# J6_output.net
KiCad netlist of a schematic drawn in EAGLE
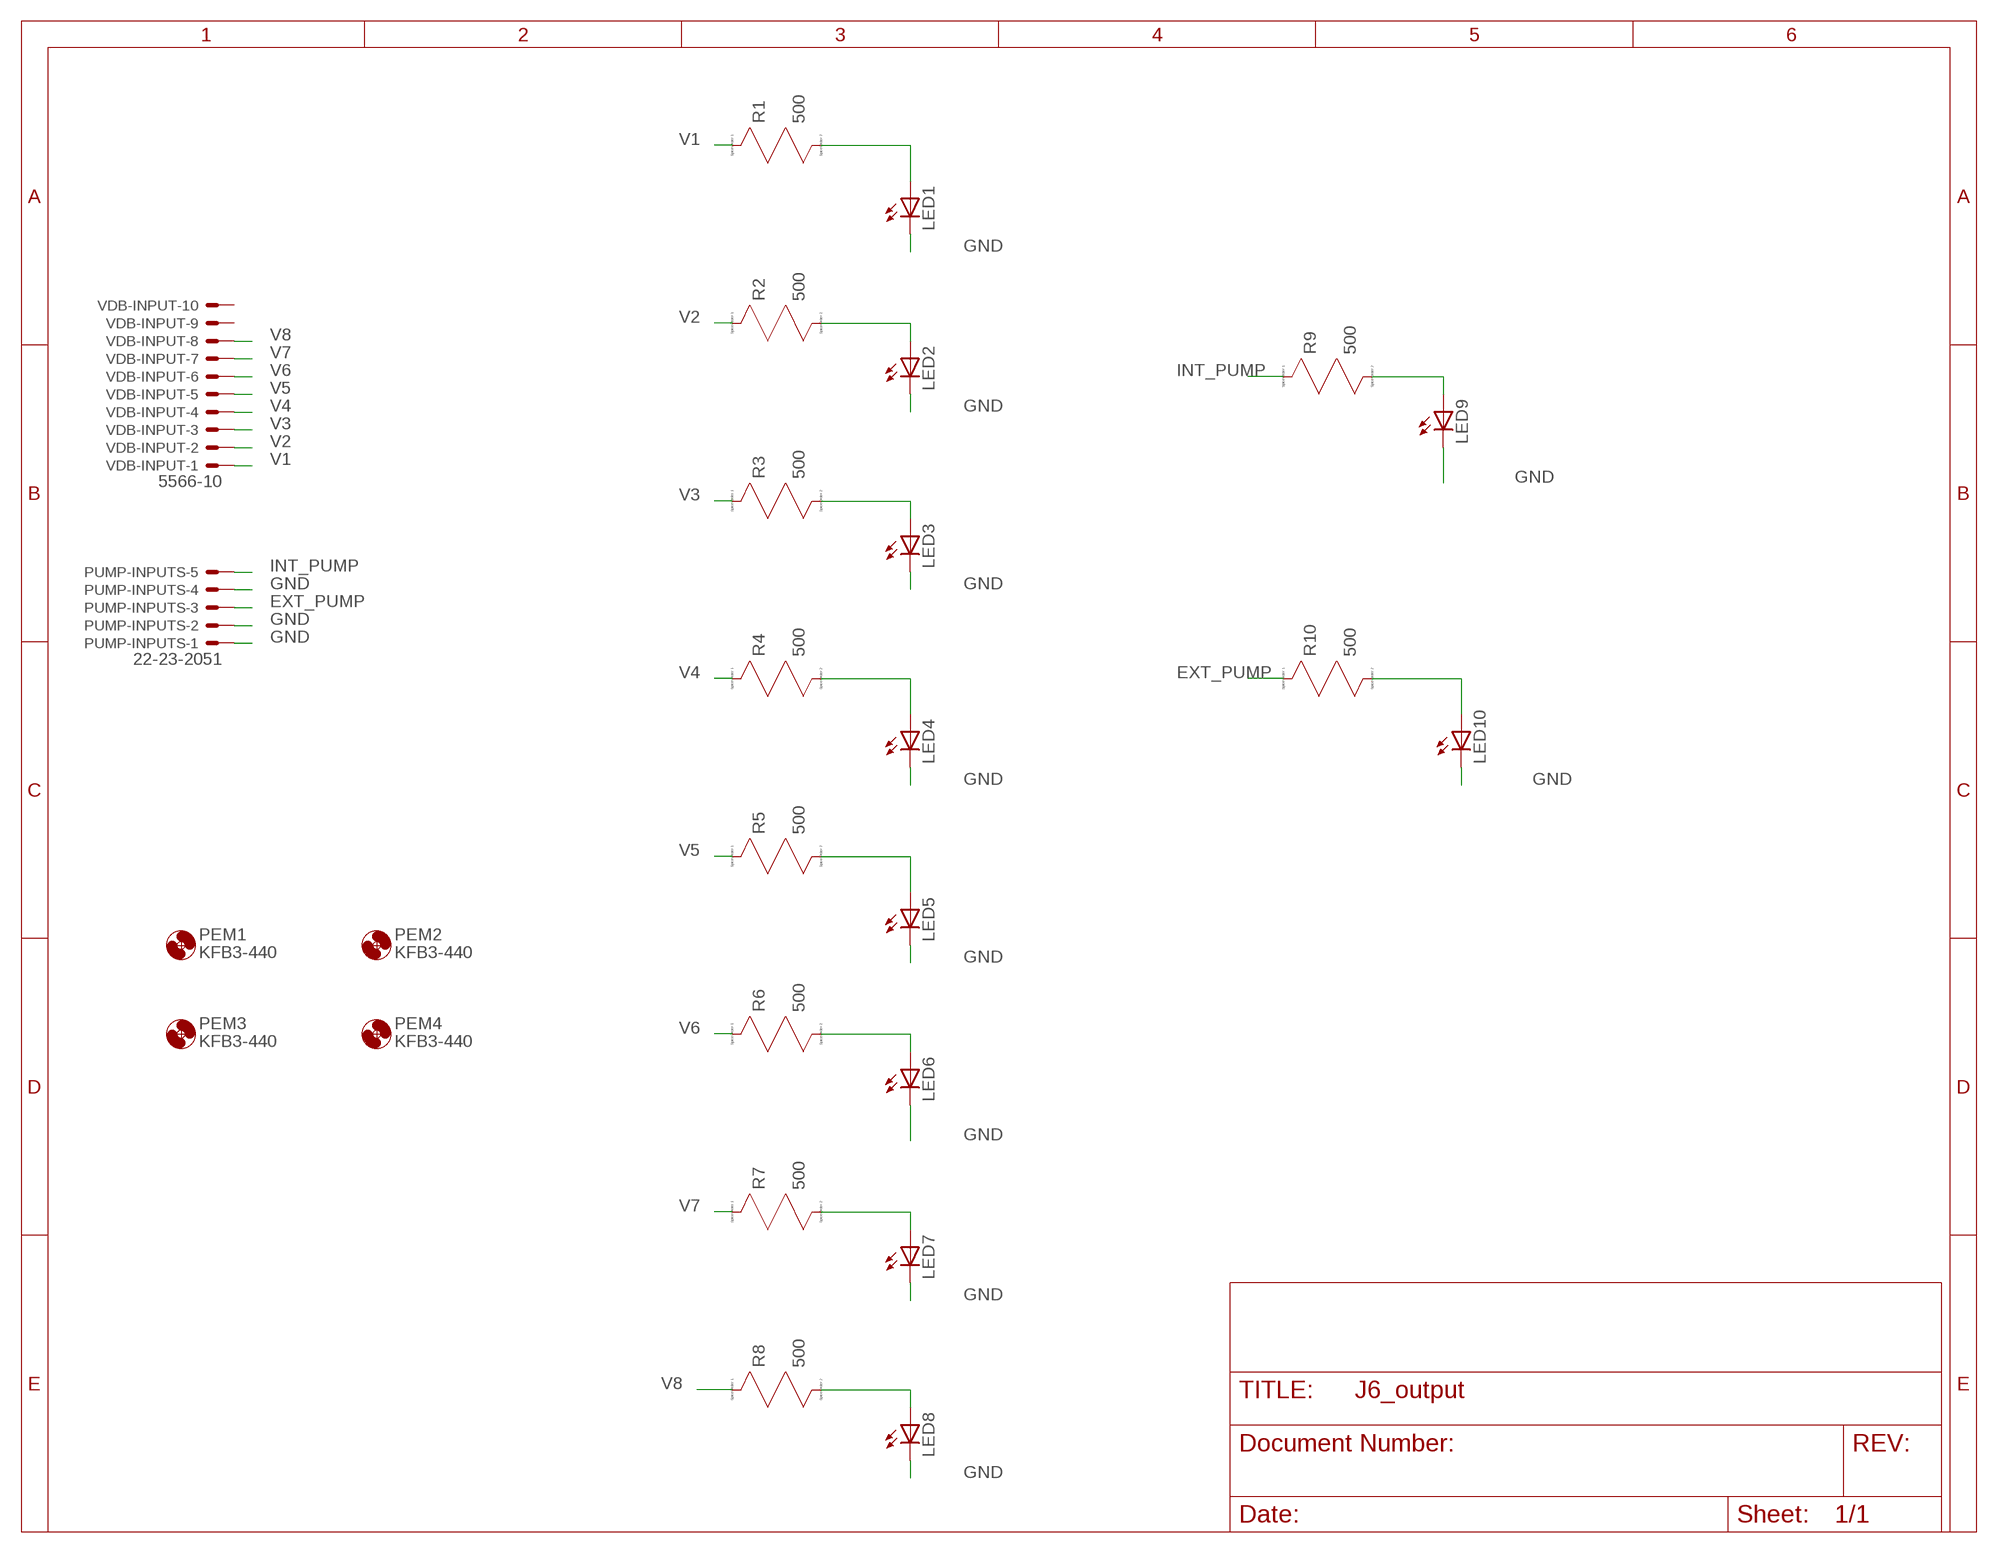
[diagram p0: schematic, sheet 1]

(export (version "E")
  (design (tool "Eeschema 10.0.6"))
  (components
    (comp (ref "LED1")
      (value "LED10MM")
      (footprint "eagle-import:LED10MM")
      (libsource (lib "eagle-import") (part "LED10MM"))
    )
    (comp (ref "LED2")
      (value "LED10MM")
      (footprint "eagle-import:LED10MM")
      (libsource (lib "eagle-import") (part "LED10MM"))
    )
    (comp (ref "LED3")
      (value "LED10MM")
      (footprint "eagle-import:LED10MM")
      (libsource (lib "eagle-import") (part "LED10MM"))
    )
    (comp (ref "LED4")
      (value "LED10MM")
      (footprint "eagle-import:LED10MM")
      (libsource (lib "eagle-import") (part "LED10MM"))
    )
    (comp (ref "LED5")
      (value "LED10MM")
      (footprint "eagle-import:LED10MM")
      (libsource (lib "eagle-import") (part "LED10MM"))
    )
    (comp (ref "LED6")
      (value "LED10MM")
      (footprint "eagle-import:LED10MM")
      (libsource (lib "eagle-import") (part "LED10MM"))
    )
    (comp (ref "LED7")
      (value "LED10MM")
      (footprint "eagle-import:LED10MM")
      (libsource (lib "eagle-import") (part "LED10MM"))
    )
    (comp (ref "LED8")
      (value "LED10MM")
      (footprint "eagle-import:LED10MM")
      (libsource (lib "eagle-import") (part "LED10MM"))
    )
    (comp (ref "LED9")
      (value "LED10MM")
      (footprint "eagle-import:LED10MM")
      (libsource (lib "eagle-import") (part "LED10MM"))
    )
    (comp (ref "LED10")
      (value "LED10MM")
      (footprint "eagle-import:LED10MM")
      (libsource (lib "eagle-import") (part "LED10MM"))
    )
    (comp (ref "PEM1")
      (value "KFB3-440")
      (footprint "eagle-import:KFB3-440")
      (libsource (lib "eagle-import") (part "KFB3-440"))
    )
    (comp (ref "PEM2")
      (value "KFB3-440")
      (footprint "eagle-import:KFB3-440")
      (libsource (lib "eagle-import") (part "KFB3-440"))
    )
    (comp (ref "PEM3")
      (value "KFB3-440")
      (footprint "eagle-import:KFB3-440")
      (libsource (lib "eagle-import") (part "KFB3-440"))
    )
    (comp (ref "PEM4")
      (value "KFB3-440")
      (footprint "eagle-import:KFB3-440")
      (libsource (lib "eagle-import") (part "KFB3-440"))
    )
    (comp (ref "PUMP-INPUTS")
      (value "22-23-2051")
      (footprint "eagle-import:22-23-2051")
      (fields (field (name "OC_NEWARK") "unknown"))
      (libsource (lib "eagle-import") (part "22-23-2051"))
    )
    (comp (ref "R1")
      (value "500")
      (footprint "eagle-import:R0805")
      (fields (field (name "MF") "BC  COMPONENTS") (field (name "MPN") "SFR2500001401FR500"))
      (libsource (lib "eagle-import") (part "RES"))
    )
    (comp (ref "R2")
      (value "500")
      (footprint "eagle-import:R0805")
      (fields (field (name "MF") "BC  COMPONENTS") (field (name "MPN") "SFR2500001401FR500"))
      (libsource (lib "eagle-import") (part "RES"))
    )
    (comp (ref "R3")
      (value "500")
      (footprint "eagle-import:R0805")
      (fields (field (name "MF") "BC  COMPONENTS") (field (name "MPN") "SFR2500001401FR500"))
      (libsource (lib "eagle-import") (part "RES"))
    )
    (comp (ref "R4")
      (value "500")
      (footprint "eagle-import:R0805")
      (fields (field (name "MF") "BC  COMPONENTS") (field (name "MPN") "SFR2500001401FR500"))
      (libsource (lib "eagle-import") (part "RES"))
    )
    (comp (ref "R5")
      (value "500")
      (footprint "eagle-import:R0805")
      (fields (field (name "MF") "BC  COMPONENTS") (field (name "MPN") "SFR2500001401FR500"))
      (libsource (lib "eagle-import") (part "RES"))
    )
    (comp (ref "R6")
      (value "500")
      (footprint "eagle-import:R0805")
      (fields (field (name "MF") "BC  COMPONENTS") (field (name "MPN") "SFR2500001401FR500"))
      (libsource (lib "eagle-import") (part "RES"))
    )
    (comp (ref "R7")
      (value "500")
      (footprint "eagle-import:R0805")
      (fields (field (name "MF") "BC  COMPONENTS") (field (name "MPN") "SFR2500001401FR500"))
      (libsource (lib "eagle-import") (part "RES"))
    )
    (comp (ref "R8")
      (value "500")
      (footprint "eagle-import:R0805")
      (fields (field (name "MF") "BC  COMPONENTS") (field (name "MPN") "SFR2500001401FR500"))
      (libsource (lib "eagle-import") (part "RES"))
    )
    (comp (ref "R9")
      (value "500")
      (footprint "eagle-import:R0805")
      (fields (field (name "MF") "BC  COMPONENTS") (field (name "MPN") "SFR2500001401FR500"))
      (libsource (lib "eagle-import") (part "RES"))
    )
    (comp (ref "R10")
      (value "500")
      (footprint "eagle-import:R0805")
      (fields (field (name "MF") "BC  COMPONENTS") (field (name "MPN") "SFR2500001401FR500"))
      (libsource (lib "eagle-import") (part "RES"))
    )
    (comp (ref "VDB-INPUT")
      (value "5566-10")
      (footprint "eagle-import:5566-10")
      (fields
        (field (name "MF") "MOLEX")
        (field (name "MPN") "39-29-6108")
        (field (name "OC_NEWARK") "07H6587")
      )
      (libsource (lib "eagle-import") (part "5566-10"))
    )
  )
  (nets
    (net (code "1") (name "/EXT_PUMP") (class "Default")
      (node (ref "PUMP-INPUTS") (pin "3") (pinfunction "S_3") (pintype "passive"))
      (node (ref "R10") (pin "1") (pinfunction "A_1") (pintype "passive"))
    )
    (net (code "2") (name "/GND") (class "Default")
      (node (ref "LED1") (pin "K") (pinfunction "C_K") (pintype "passive"))
      (node (ref "LED10") (pin "K") (pinfunction "C_K") (pintype "passive"))
      (node (ref "LED2") (pin "K") (pinfunction "C_K") (pintype "passive"))
      (node (ref "LED3") (pin "K") (pinfunction "C_K") (pintype "passive"))
      (node (ref "LED4") (pin "K") (pinfunction "C_K") (pintype "passive"))
      (node (ref "LED5") (pin "K") (pinfunction "C_K") (pintype "passive"))
      (node (ref "LED6") (pin "K") (pinfunction "C_K") (pintype "passive"))
      (node (ref "LED7") (pin "K") (pinfunction "C_K") (pintype "passive"))
      (node (ref "LED8") (pin "K") (pinfunction "C_K") (pintype "passive"))
      (node (ref "LED9") (pin "K") (pinfunction "C_K") (pintype "passive"))
      (node (ref "PUMP-INPUTS") (pin "1") (pinfunction "S_1") (pintype "passive"))
      (node (ref "PUMP-INPUTS") (pin "2") (pinfunction "S_2") (pintype "passive"))
      (node (ref "PUMP-INPUTS") (pin "4") (pinfunction "S_4") (pintype "passive"))
    )
    (net (code "3") (name "/INT_PUMP") (class "Default")
      (node (ref "PUMP-INPUTS") (pin "5") (pinfunction "S_5") (pintype "passive"))
      (node (ref "R9") (pin "1") (pinfunction "A_1") (pintype "passive"))
    )
    (net (code "4") (name "/V1") (class "Default")
      (node (ref "R1") (pin "1") (pinfunction "A_1") (pintype "passive"))
      (node (ref "VDB-INPUT") (pin "1") (pinfunction "S_1") (pintype "passive"))
    )
    (net (code "5") (name "/V2") (class "Default")
      (node (ref "R2") (pin "1") (pinfunction "A_1") (pintype "passive"))
      (node (ref "VDB-INPUT") (pin "2") (pinfunction "S_2") (pintype "passive"))
    )
    (net (code "6") (name "/V3") (class "Default")
      (node (ref "R3") (pin "1") (pinfunction "A_1") (pintype "passive"))
      (node (ref "VDB-INPUT") (pin "3") (pinfunction "S_3") (pintype "passive"))
    )
    (net (code "7") (name "/V4") (class "Default")
      (node (ref "R4") (pin "1") (pinfunction "A_1") (pintype "passive"))
      (node (ref "VDB-INPUT") (pin "4") (pinfunction "S_4") (pintype "passive"))
    )
    (net (code "8") (name "/V5") (class "Default")
      (node (ref "R5") (pin "1") (pinfunction "A_1") (pintype "passive"))
      (node (ref "VDB-INPUT") (pin "5") (pinfunction "S_5") (pintype "passive"))
    )
    (net (code "9") (name "/V6") (class "Default")
      (node (ref "R6") (pin "1") (pinfunction "A_1") (pintype "passive"))
      (node (ref "VDB-INPUT") (pin "6") (pinfunction "S_6") (pintype "passive"))
    )
    (net (code "10") (name "/V7") (class "Default")
      (node (ref "R7") (pin "1") (pinfunction "A_1") (pintype "passive"))
      (node (ref "VDB-INPUT") (pin "7") (pinfunction "S_7") (pintype "passive"))
    )
    (net (code "11") (name "/V8") (class "Default")
      (node (ref "R8") (pin "1") (pinfunction "A_1") (pintype "passive"))
      (node (ref "VDB-INPUT") (pin "8") (pinfunction "S_8") (pintype "passive"))
    )
    (net (code "12") (name "Net-(R1-B)") (class "Default")
      (node (ref "LED1") (pin "A") (pinfunction "A_A") (pintype "passive"))
      (node (ref "R1") (pin "2") (pinfunction "B_2") (pintype "passive"))
    )
    (net (code "13") (name "Net-(R2-B)") (class "Default")
      (node (ref "LED2") (pin "A") (pinfunction "A_A") (pintype "passive"))
      (node (ref "R2") (pin "2") (pinfunction "B_2") (pintype "passive"))
    )
    (net (code "14") (name "Net-(R3-B)") (class "Default")
      (node (ref "LED3") (pin "A") (pinfunction "A_A") (pintype "passive"))
      (node (ref "R3") (pin "2") (pinfunction "B_2") (pintype "passive"))
    )
    (net (code "15") (name "Net-(R4-B)") (class "Default")
      (node (ref "LED4") (pin "A") (pinfunction "A_A") (pintype "passive"))
      (node (ref "R4") (pin "2") (pinfunction "B_2") (pintype "passive"))
    )
    (net (code "16") (name "Net-(R5-B)") (class "Default")
      (node (ref "LED5") (pin "A") (pinfunction "A_A") (pintype "passive"))
      (node (ref "R5") (pin "2") (pinfunction "B_2") (pintype "passive"))
    )
    (net (code "17") (name "Net-(R6-B)") (class "Default")
      (node (ref "LED6") (pin "A") (pinfunction "A_A") (pintype "passive"))
      (node (ref "R6") (pin "2") (pinfunction "B_2") (pintype "passive"))
    )
    (net (code "18") (name "Net-(R7-B)") (class "Default")
      (node (ref "LED7") (pin "A") (pinfunction "A_A") (pintype "passive"))
      (node (ref "R7") (pin "2") (pinfunction "B_2") (pintype "passive"))
    )
    (net (code "19") (name "Net-(R8-B)") (class "Default")
      (node (ref "LED8") (pin "A") (pinfunction "A_A") (pintype "passive"))
      (node (ref "R8") (pin "2") (pinfunction "B_2") (pintype "passive"))
    )
    (net (code "20") (name "Net-(R9-B)") (class "Default")
      (node (ref "LED9") (pin "A") (pinfunction "A_A") (pintype "passive"))
      (node (ref "R9") (pin "2") (pinfunction "B_2") (pintype "passive"))
    )
    (net (code "21") (name "Net-(R10-B)") (class "Default")
      (node (ref "LED10") (pin "A") (pinfunction "A_A") (pintype "passive"))
      (node (ref "R10") (pin "2") (pinfunction "B_2") (pintype "passive"))
    )
    (net (code "22") (name "unconnected-(VDB-INPUTB-S-Pad10)") (class "Default")
      (node (ref "VDB-INPUT") (pin "10") (pinfunction "S_10") (pintype "passive"))
    )
    (net (code "23") (name "unconnected-(VDB-INPUTJ-S-Pad9)") (class "Default")
      (node (ref "VDB-INPUT") (pin "9") (pinfunction "S_9") (pintype "passive"))
    )
  )
)
